# adaptor.net
KiCad netlist of a schematic drawn in EAGLE
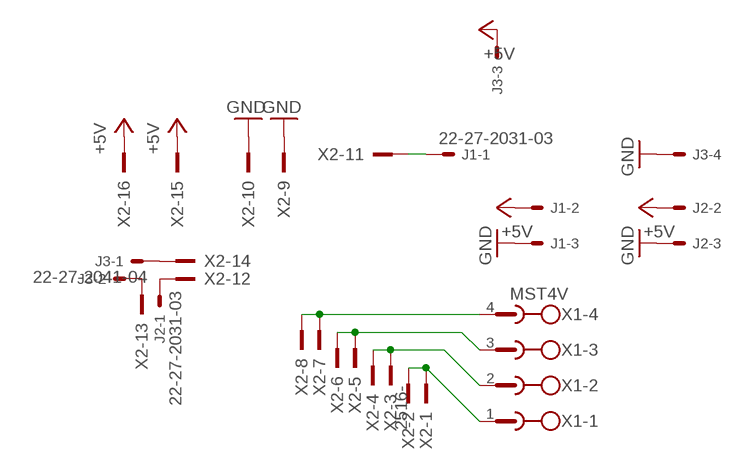
[diagram p0: schematic, sheet 1]

(export (version "E")
  (design (tool "Eeschema 10.0.6"))
  (components
    (comp (ref "J1")
      (value "22-27-2031-03")
      (footprint "eagle-import:6410-03")
      (libsource (lib "eagle-import") (part "22-?-0327-2031"))
    )
    (comp (ref "J2")
      (value "22-27-2031-03")
      (footprint "eagle-import:6410-03")
      (libsource (lib "eagle-import") (part "22-?-0327-2031"))
    )
    (comp (ref "J3")
      (value "22-27-2041-04")
      (footprint "eagle-import:6410-04")
      (libsource (lib "eagle-import") (part "22-?-0427-2041"))
    )
    (comp (ref "X1")
      (value "MST4V")
      (footprint "eagle-import:MSTBV4")
      (libsource (lib "eagle-import") (part "MST4V"))
    )
    (comp (ref "X2")
      (value "2516-")
      (footprint "eagle-import:PAK100_2500-16")
      (libsource (lib "eagle-import") (part "2516-"))
    )
  )
  (nets
    (net (code "1") (name "+5V") (class "Default")
      (node (ref "J1") (pin "2") (pinfunction "S_2") (pintype "passive"))
      (node (ref "J2") (pin "2") (pinfunction "S_2") (pintype "passive"))
      (node (ref "J3") (pin "3") (pinfunction "S_3") (pintype "passive"))
      (node (ref "X2") (pin "15") (pinfunction "KL_15") (pintype "passive"))
      (node (ref "X2") (pin "16") (pinfunction "KL_16") (pintype "passive"))
    )
    (net (code "2") (name "GND") (class "Default")
      (node (ref "J1") (pin "3") (pinfunction "S_3") (pintype "passive"))
      (node (ref "J2") (pin "3") (pinfunction "S_3") (pintype "passive"))
      (node (ref "J3") (pin "4") (pinfunction "S_4") (pintype "passive"))
      (node (ref "X2") (pin "10") (pinfunction "KL_10") (pintype "passive"))
      (node (ref "X2") (pin "9") (pinfunction "KL_9") (pintype "passive"))
    )
    (net (code "3") (name "Net-(J1A-S)") (class "Default")
      (node (ref "J1") (pin "1") (pinfunction "S_1") (pintype "passive"))
      (node (ref "X2") (pin "11") (pinfunction "KL_11") (pintype "passive"))
    )
    (net (code "4") (name "Net-(J2A-S)") (class "Default")
      (node (ref "J2") (pin "1") (pinfunction "S_1") (pintype "passive"))
      (node (ref "X2") (pin "12") (pinfunction "KL_12") (pintype "passive"))
    )
    (net (code "5") (name "Net-(J3A-S)") (class "Default")
      (node (ref "J3") (pin "1") (pinfunction "S_1") (pintype "passive"))
      (node (ref "X2") (pin "14") (pinfunction "KL_14") (pintype "passive"))
    )
    (net (code "6") (name "Net-(J3B-S)") (class "Default")
      (node (ref "J3") (pin "2") (pinfunction "S_2") (pintype "passive"))
      (node (ref "X2") (pin "13") (pinfunction "KL_13") (pintype "passive"))
    )
    (net (code "7") (name "Net-(X1B-1)") (class "Default")
      (node (ref "X1") (pin "2") (pinfunction "1_2") (pintype "passive"))
      (node (ref "X2") (pin "3") (pinfunction "KL_3") (pintype "passive"))
      (node (ref "X2") (pin "4") (pinfunction "KL_4") (pintype "passive"))
    )
    (net (code "8") (name "Net-(X1C-1)") (class "Default")
      (node (ref "X1") (pin "3") (pinfunction "1_3") (pintype "passive"))
      (node (ref "X2") (pin "5") (pinfunction "KL_5") (pintype "passive"))
      (node (ref "X2") (pin "6") (pinfunction "KL_6") (pintype "passive"))
    )
    (net (code "9") (name "Net-(X1D-1)") (class "Default")
      (node (ref "X1") (pin "4") (pinfunction "1_4") (pintype "passive"))
      (node (ref "X2") (pin "7") (pinfunction "KL_7") (pintype "passive"))
      (node (ref "X2") (pin "8") (pinfunction "KL_8") (pintype "passive"))
    )
    (net (code "10") (name "Net-(X2A-KL)") (class "Default")
      (node (ref "X1") (pin "1") (pinfunction "1_1") (pintype "passive"))
      (node (ref "X2") (pin "1") (pinfunction "KL_1") (pintype "passive"))
      (node (ref "X2") (pin "2") (pinfunction "KL_2") (pintype "passive"))
    )
  )
)
